# RC_Transmitter.net
KiCad netlist of a schematic drawn in EasyEDA Pro
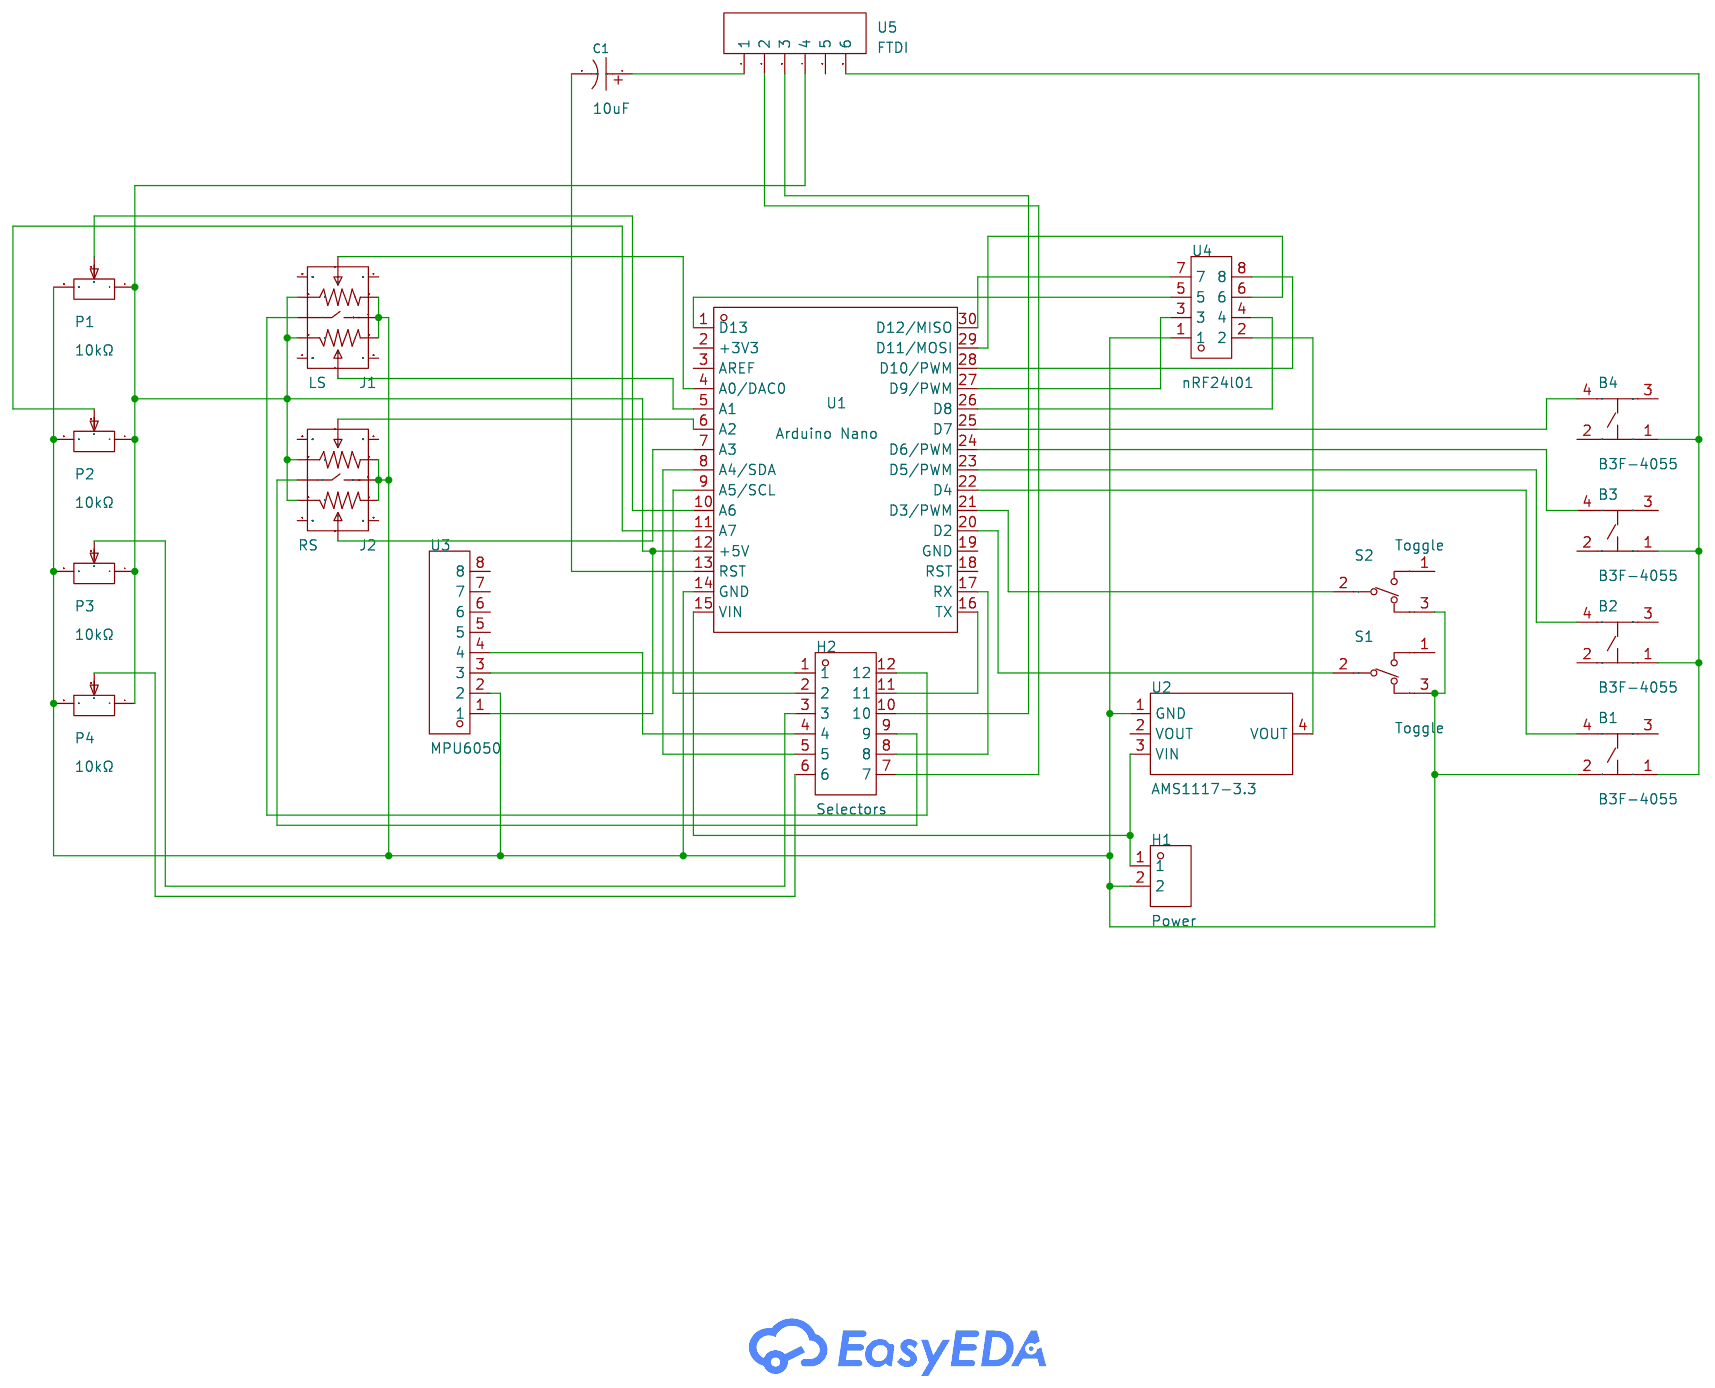
[diagram p0: schematic sheet]

(export (version "E")
  (design (tool "Eeschema 10.0.6"))
  (components
    (comp (ref "B1")
      (value "B3F-4055")
      (footprint "easyedapro:KEY-TH_4P-L12.0-W12.0-P5.00-LS13.4-EH")
      (fields (field (name "Manufacturer") "OMRON(欧姆龙)"))
      (libsource (lib "easyedapro") (part "B3F-4055"))
    )
    (comp (ref "B2")
      (value "B3F-4055")
      (footprint "easyedapro:KEY-TH_4P-L12.0-W12.0-P5.00-LS13.4-EH")
      (fields (field (name "Manufacturer") "OMRON(欧姆龙)"))
      (libsource (lib "easyedapro") (part "B3F-4055"))
    )
    (comp (ref "B3")
      (value "B3F-4055")
      (footprint "easyedapro:KEY-TH_4P-L12.0-W12.0-P5.00-LS13.4-EH")
      (fields (field (name "Manufacturer") "OMRON(欧姆龙)"))
      (libsource (lib "easyedapro") (part "B3F-4055"))
    )
    (comp (ref "B4")
      (value "B3F-4055")
      (footprint "easyedapro:KEY-TH_4P-L12.0-W12.0-P5.00-LS13.4-EH")
      (fields (field (name "Manufacturer") "OMRON(欧姆龙)"))
      (libsource (lib "easyedapro") (part "B3F-4055"))
    )
    (comp (ref "C1")
      (value "10uF")
      (footprint "easyedapro:CAP-TH_BD5.0-P2.00-D0.8-FD")
      (fields (field (name "Manufacturer Part") "RD1H106M05011PC") (field (name "Manufacturer") "SAMWHA(三和)"))
      (libsource (lib "easyedapro") (part "RD1H106M05011PC"))
    )
    (comp (ref "H1")
      (value "Power")
      (footprint "easyedapro:HDR-TH_2P-P2.54-V-M_5")
      (fields (field (name "Manufacturer") "HCTL(华灿天禄)"))
      (libsource (lib "easyedapro") (part "PZ254-1-02-Z-C"))
    )
    (comp (ref "H2")
      (value "Selectors")
      (footprint "easyedapro:HDR-TH_12P-P2.54-V-M-R3-C4-S2.54")
      (fields (field (name "Manufacturer") "hanxia(韩下)"))
      (libsource (lib "easyedapro") (part "HX PZ2.54-3X4P ZZ"))
    )
    (comp (ref "J1")
      (value "LS")
      (footprint "easyedapro:JOYTICK-TH_YF16S-FL7.2-B5KB-45-10-Y_1")
      (fields (field (name "Manufacturer") "YTL(亚特联)"))
      (libsource (lib "easyedapro") (part "YK16S-L7.2-B10KA(32-8)-G-A29"))
    )
    (comp (ref "J2")
      (value "RS")
      (footprint "easyedapro:JOYTICK-TH_YF16S-FL7.2-B5KB-45-10-Y_1")
      (fields (field (name "Manufacturer") "YTL(亚特联)"))
      (libsource (lib "easyedapro") (part "YK16S-L7.2-B10KA(32-8)-G-A29"))
    )
    (comp (ref "P1")
      (value "10kΩ")
      (footprint "easyedapro:RES-ADJ-TH_RK1631110U1Q")
      (description "Resistance: Tolerance:±20% Tolerance:±20% Rated Voltage:5V Power(Watts):100mW Turns:-")
      (fields
        (field (name "Manufacturer Part") "RK1631110U1Q")
        (field (name "Manufacturer") "ALPSALPINE(阿尔卑斯阿尔派)")
      )
      (libsource (lib "easyedapro") (part "RK1631110U1Q"))
    )
    (comp (ref "P2")
      (value "10kΩ")
      (footprint "easyedapro:RES-ADJ-TH_RK1631110U1Q")
      (description "Resistance: Tolerance:±20% Tolerance:±20% Rated Voltage:5V Power(Watts):100mW Turns:-")
      (fields
        (field (name "Manufacturer Part") "RK1631110U1Q")
        (field (name "Manufacturer") "ALPSALPINE(阿尔卑斯阿尔派)")
      )
      (libsource (lib "easyedapro") (part "RK1631110U1Q"))
    )
    (comp (ref "P3")
      (value "10kΩ")
      (footprint "easyedapro:RES-ADJ-TH_RK1631110U1Q")
      (description "Resistance: Tolerance:±20% Tolerance:±20% Rated Voltage:5V Power(Watts):100mW Turns:-")
      (fields
        (field (name "Manufacturer Part") "RK1631110U1Q")
        (field (name "Manufacturer") "ALPSALPINE(阿尔卑斯阿尔派)")
      )
      (libsource (lib "easyedapro") (part "RK1631110U1Q"))
    )
    (comp (ref "P4")
      (value "10kΩ")
      (footprint "easyedapro:RES-ADJ-TH_RK1631110U1Q")
      (description "Resistance: Tolerance:±20% Tolerance:±20% Rated Voltage:5V Power(Watts):100mW Turns:-")
      (fields
        (field (name "Manufacturer Part") "RK1631110U1Q")
        (field (name "Manufacturer") "ALPSALPINE(阿尔卑斯阿尔派)")
      )
      (libsource (lib "easyedapro") (part "RK1631110U1Q"))
    )
    (comp (ref "S1")
      (value "Toggle")
      (footprint "easyedapro:SW-TH_ST-0-103-A01")
      (fields (field (name "Manufacturer") "YUEN FUNG(源丰)"))
      (libsource (lib "easyedapro") (part "ST-0-103-A01-T000-RS"))
    )
    (comp (ref "S2")
      (value "Toggle")
      (footprint "easyedapro:SW-TH_ST-0-103-A01")
      (fields (field (name "Manufacturer") "YUEN FUNG(源丰)"))
      (libsource (lib "easyedapro") (part "ST-0-103-A01-T000-RS"))
    )
    (comp (ref "U1")
      (value "Arduino Nano")
      (footprint "easyedapro:MOD-TH_ABX00028")
      (fields (field (name "Manufacturer") "arduino"))
      (libsource (lib "easyedapro") (part "ABX00028"))
    )
    (comp (ref "U2")
      (value "AMS1117-3.3")
      (footprint "easyedapro:SOT-223-3_L6.5-W3.4-P2.30-LS7.0-BR")
      (fields (field (name "Manufacturer") "AMS"))
      (libsource (lib "easyedapro") (part "AMS1117-3.3"))
    )
    (comp (ref "U3")
      (value "MPU6050")
      (footprint "easyedapro:HDR-TH_8P-P2.54-V-F")
      (fields (field (name "Manufacturer") "kinghelm(金航标)"))
      (libsource (lib "easyedapro") (part "KH-2.54FH-1X8P-H8.5"))
    )
    (comp (ref "U4")
      (value "nRF24l01")
      (footprint "easyedapro:HDR-TH_8P-P2.54-V-F-R2-C4-S2.54")
      (fields (field (name "Manufacturer") "ZHOURI(洲日)"))
      (libsource (lib "easyedapro") (part "2.54-2*4"))
    )
    (comp (ref "U5")
      (value "FTDI")
      (footprint "easyedapro:HDR-TH_6P-P2.54-V-M-1")
      (fields (field (name "Manufacturer") "BOOMELE(博穆精密)"))
      (libsource (lib "easyedapro") (part "Header-Male-2.54_1x6"))
    )
  )
  (nets
    (net (code "1") (name "Net-(B1-Pad1)") (class "Default")
      (node (ref "B1") (pin "1") (pinfunction "1_1") (pintype "unspecified"))
      (node (ref "B2") (pin "1") (pinfunction "1_1") (pintype "unspecified"))
      (node (ref "B3") (pin "1") (pinfunction "1_1") (pintype "unspecified"))
      (node (ref "B4") (pin "1") (pinfunction "1_1") (pintype "unspecified"))
      (node (ref "U5") (pin "6") (pinfunction "6_6") (pintype "input"))
    )
    (net (code "2") (name "Net-(C1-Pad1)") (class "Default")
      (node (ref "C1") (pin "1") (pinfunction "1_1") (pintype "input"))
      (node (ref "U5") (pin "1") (pinfunction "1_1") (pintype "input"))
    )
    (net (code "3") (name "Net-(C1-Pad2)") (class "Default")
      (node (ref "C1") (pin "2") (pinfunction "2_2") (pintype "input"))
      (node (ref "U1") (pin "13") (pinfunction "RST_13") (pintype "unspecified"))
    )
    (net (code "4") (name "Net-(H2-Pad1)") (class "Default")
      (node (ref "H2") (pin "1") (pinfunction "1_1") (pintype "unspecified"))
      (node (ref "U3") (pin "3") (pinfunction "3_3") (pintype "unspecified"))
    )
    (net (code "5") (name "Net-(H2-Pad3)") (class "Default")
      (node (ref "H2") (pin "3") (pinfunction "3_3") (pintype "unspecified"))
      (node (ref "P3") (pin "2") (pinfunction "2_2") (pintype "input"))
    )
    (net (code "6") (name "Net-(H2-Pad4)") (class "Default")
      (node (ref "H2") (pin "4") (pinfunction "4_4") (pintype "unspecified"))
      (node (ref "U3") (pin "4") (pinfunction "4_4") (pintype "unspecified"))
    )
    (net (code "7") (name "Net-(H2-Pad6)") (class "Default")
      (node (ref "H2") (pin "6") (pinfunction "6_6") (pintype "unspecified"))
      (node (ref "P4") (pin "2") (pinfunction "2_2") (pintype "input"))
    )
    (net (code "8") (name "Net-(H2-Pad7)") (class "Default")
      (node (ref "H2") (pin "7") (pinfunction "7_7") (pintype "unspecified"))
      (node (ref "U5") (pin "2") (pinfunction "2_2") (pintype "input"))
    )
    (net (code "9") (name "Net-(H2-Pad9)") (class "Default")
      (node (ref "H2") (pin "9") (pinfunction "9_9") (pintype "unspecified"))
      (node (ref "J2") (pin "7") (pinfunction "7_7") (pintype "unspecified"))
    )
    (net (code "10") (name "Net-(H2-Pad10)") (class "Default")
      (node (ref "H2") (pin "10") (pinfunction "10_10") (pintype "unspecified"))
      (node (ref "U5") (pin "3") (pinfunction "3_3") (pintype "input"))
    )
    (net (code "11") (name "Net-(H2-Pad12)") (class "Default")
      (node (ref "H2") (pin "12") (pinfunction "12_12") (pintype "unspecified"))
      (node (ref "J1") (pin "7") (pinfunction "7_7") (pintype "unspecified"))
    )
    (net (code "12") (name "Net-(U1-+5V)") (class "Default")
      (node (ref "J1") (pin "3") (pinfunction "3_3") (pintype "unspecified"))
      (node (ref "J1") (pin "6") (pinfunction "6_6") (pintype "unspecified"))
      (node (ref "J2") (pin "3") (pinfunction "3_3") (pintype "unspecified"))
      (node (ref "J2") (pin "6") (pinfunction "6_6") (pintype "unspecified"))
      (node (ref "P1") (pin "1") (pinfunction "1_1") (pintype "input"))
      (node (ref "P2") (pin "1") (pinfunction "1_1") (pintype "input"))
      (node (ref "P3") (pin "1") (pinfunction "1_1") (pintype "input"))
      (node (ref "P4") (pin "1") (pinfunction "1_1") (pintype "input"))
      (node (ref "U1") (pin "12") (pinfunction "+5V_12") (pintype "unspecified"))
      (node (ref "U3") (pin "1") (pinfunction "1_1") (pintype "unspecified"))
      (node (ref "U5") (pin "4") (pinfunction "4_4") (pintype "input"))
    )
    (net (code "13") (name "Net-(U1-A0{slash}DAC0)") (class "Default")
      (node (ref "J1") (pin "2") (pinfunction "2_2") (pintype "unspecified"))
      (node (ref "U1") (pin "4") (pinfunction "A0/DAC0_4") (pintype "unspecified"))
    )
    (net (code "14") (name "Net-(U1-A1)") (class "Default")
      (node (ref "J1") (pin "5") (pinfunction "5_5") (pintype "unspecified"))
      (node (ref "U1") (pin "5") (pinfunction "A1_5") (pintype "unspecified"))
    )
    (net (code "15") (name "Net-(U1-A2)") (class "Default")
      (node (ref "J2") (pin "2") (pinfunction "2_2") (pintype "unspecified"))
      (node (ref "U1") (pin "6") (pinfunction "A2_6") (pintype "unspecified"))
    )
    (net (code "16") (name "Net-(U1-A3)") (class "Default")
      (node (ref "J2") (pin "5") (pinfunction "5_5") (pintype "unspecified"))
      (node (ref "U1") (pin "7") (pinfunction "A3_7") (pintype "unspecified"))
    )
    (net (code "17") (name "Net-(U1-A4{slash}SDA)") (class "Default")
      (node (ref "H2") (pin "5") (pinfunction "5_5") (pintype "unspecified"))
      (node (ref "U1") (pin "8") (pinfunction "A4/SDA_8") (pintype "unspecified"))
    )
    (net (code "18") (name "Net-(U1-A5{slash}SCL)") (class "Default")
      (node (ref "H2") (pin "2") (pinfunction "2_2") (pintype "unspecified"))
      (node (ref "U1") (pin "9") (pinfunction "A5/SCL_9") (pintype "unspecified"))
    )
    (net (code "19") (name "Net-(U1-A6)") (class "Default")
      (node (ref "P1") (pin "2") (pinfunction "2_2") (pintype "input"))
      (node (ref "U1") (pin "10") (pinfunction "A6_10") (pintype "unspecified"))
    )
    (net (code "20") (name "Net-(U1-A7)") (class "Default")
      (node (ref "P2") (pin "2") (pinfunction "2_2") (pintype "input"))
      (node (ref "U1") (pin "11") (pinfunction "A7_11") (pintype "unspecified"))
    )
    (net (code "21") (name "Net-(U1-D2)") (class "Default")
      (node (ref "S1") (pin "2") (pinfunction "2_2") (pintype "unspecified"))
      (node (ref "U1") (pin "20") (pinfunction "D2_20") (pintype "unspecified"))
    )
    (net (code "22") (name "Net-(U1-D3{slash}PWM)") (class "Default")
      (node (ref "S2") (pin "2") (pinfunction "2_2") (pintype "unspecified"))
      (node (ref "U1") (pin "21") (pinfunction "D3/PWM_21") (pintype "unspecified"))
    )
    (net (code "23") (name "Net-(U1-D4)") (class "Default")
      (node (ref "B1") (pin "4") (pinfunction "4_4") (pintype "unspecified"))
      (node (ref "U1") (pin "22") (pinfunction "D4_22") (pintype "unspecified"))
    )
    (net (code "24") (name "Net-(U1-D5{slash}PWM)") (class "Default")
      (node (ref "B2") (pin "4") (pinfunction "4_4") (pintype "unspecified"))
      (node (ref "U1") (pin "23") (pinfunction "D5/PWM_23") (pintype "unspecified"))
    )
    (net (code "25") (name "Net-(U1-D6{slash}PWM)") (class "Default")
      (node (ref "B3") (pin "4") (pinfunction "4_4") (pintype "unspecified"))
      (node (ref "U1") (pin "24") (pinfunction "D6/PWM_24") (pintype "unspecified"))
    )
    (net (code "26") (name "Net-(U1-D7)") (class "Default")
      (node (ref "B4") (pin "4") (pinfunction "4_4") (pintype "unspecified"))
      (node (ref "U1") (pin "25") (pinfunction "D7_25") (pintype "unspecified"))
    )
    (net (code "27") (name "Net-(U1-D8)") (class "Default")
      (node (ref "U1") (pin "26") (pinfunction "D8_26") (pintype "unspecified"))
      (node (ref "U4") (pin "4") (pinfunction "4_4") (pintype "unspecified"))
    )
    (net (code "28") (name "Net-(U1-D9{slash}PWM)") (class "Default")
      (node (ref "U1") (pin "27") (pinfunction "D9/PWM_27") (pintype "unspecified"))
      (node (ref "U4") (pin "3") (pinfunction "3_3") (pintype "unspecified"))
    )
    (net (code "29") (name "Net-(U1-D10{slash}PWM)") (class "Default")
      (node (ref "U1") (pin "28") (pinfunction "D10/PWM_28") (pintype "unspecified"))
      (node (ref "U4") (pin "8") (pinfunction "8_8") (pintype "unspecified"))
    )
    (net (code "30") (name "Net-(U1-D11{slash}MOSI)") (class "Default")
      (node (ref "U1") (pin "29") (pinfunction "D11/MOSI_29") (pintype "unspecified"))
      (node (ref "U4") (pin "6") (pinfunction "6_6") (pintype "unspecified"))
    )
    (net (code "31") (name "Net-(U1-D12{slash}MISO)") (class "Default")
      (node (ref "U1") (pin "30") (pinfunction "D12/MISO_30") (pintype "unspecified"))
      (node (ref "U4") (pin "7") (pinfunction "7_7") (pintype "unspecified"))
    )
    (net (code "32") (name "Net-(U1-D13)") (class "Default")
      (node (ref "U1") (pin "1") (pinfunction "D13_1") (pintype "unspecified"))
      (node (ref "U4") (pin "5") (pinfunction "5_5") (pintype "unspecified"))
    )
    (net (code "33") (name "Net-(U1-RX)") (class "Default")
      (node (ref "H2") (pin "8") (pinfunction "8_8") (pintype "unspecified"))
      (node (ref "U1") (pin "17") (pinfunction "RX_17") (pintype "unspecified"))
    )
    (net (code "34") (name "Net-(U1-TX)") (class "Default")
      (node (ref "H2") (pin "11") (pinfunction "11_11") (pintype "unspecified"))
      (node (ref "U1") (pin "16") (pinfunction "TX_16") (pintype "unspecified"))
    )
    (net (code "35") (name "Net-(U1-VIN)") (class "Default")
      (node (ref "H1") (pin "1") (pinfunction "1_1") (pintype "unspecified"))
      (node (ref "U1") (pin "15") (pinfunction "VIN_15") (pintype "unspecified"))
      (node (ref "U2") (pin "3") (pinfunction "VIN_3") (pintype "unspecified"))
    )
    (net (code "36") (name "Net-(U2-GND)") (class "Default")
      (node (ref "B1") (pin "2") (pinfunction "2_2") (pintype "unspecified"))
      (node (ref "H1") (pin "2") (pinfunction "2_2") (pintype "unspecified"))
      (node (ref "J1") (pin "1") (pinfunction "1_1") (pintype "unspecified"))
      (node (ref "J1") (pin "4") (pinfunction "4_4") (pintype "unspecified"))
      (node (ref "J1") (pin "8") (pinfunction "8_8") (pintype "unspecified"))
      (node (ref "J2") (pin "1") (pinfunction "1_1") (pintype "unspecified"))
      (node (ref "J2") (pin "4") (pinfunction "4_4") (pintype "unspecified"))
      (node (ref "J2") (pin "8") (pinfunction "8_8") (pintype "unspecified"))
      (node (ref "P1") (pin "3") (pinfunction "3_3") (pintype "input"))
      (node (ref "P2") (pin "3") (pinfunction "3_3") (pintype "input"))
      (node (ref "P3") (pin "3") (pinfunction "3_3") (pintype "input"))
      (node (ref "P4") (pin "3") (pinfunction "3_3") (pintype "input"))
      (node (ref "S1") (pin "3") (pinfunction "3_3") (pintype "unspecified"))
      (node (ref "S2") (pin "3") (pinfunction "3_3") (pintype "unspecified"))
      (node (ref "U1") (pin "14") (pinfunction "GND_14") (pintype "unspecified"))
      (node (ref "U2") (pin "1") (pinfunction "GND_1") (pintype "unspecified"))
      (node (ref "U3") (pin "2") (pinfunction "2_2") (pintype "unspecified"))
      (node (ref "U4") (pin "1") (pinfunction "1_1") (pintype "unspecified"))
    )
    (net (code "37") (name "Net-(U2-VOUT-Pad4)") (class "Default")
      (node (ref "U2") (pin "4") (pinfunction "VOUT_4") (pintype "unspecified"))
      (node (ref "U4") (pin "2") (pinfunction "2_2") (pintype "unspecified"))
    )
    (net (code "38") (name "unconnected-(B1-Pad3)") (class "Default")
      (node (ref "B1") (pin "3") (pinfunction "3_3") (pintype "unspecified"))
    )
    (net (code "39") (name "unconnected-(B2-Pad2)") (class "Default")
      (node (ref "B2") (pin "2") (pinfunction "2_2") (pintype "unspecified"))
    )
    (net (code "40") (name "unconnected-(B2-Pad3)") (class "Default")
      (node (ref "B2") (pin "3") (pinfunction "3_3") (pintype "unspecified"))
    )
    (net (code "41") (name "unconnected-(B3-Pad2)") (class "Default")
      (node (ref "B3") (pin "2") (pinfunction "2_2") (pintype "unspecified"))
    )
    (net (code "42") (name "unconnected-(B3-Pad3)") (class "Default")
      (node (ref "B3") (pin "3") (pinfunction "3_3") (pintype "unspecified"))
    )
    (net (code "43") (name "unconnected-(B4-Pad2)") (class "Default")
      (node (ref "B4") (pin "2") (pinfunction "2_2") (pintype "unspecified"))
    )
    (net (code "44") (name "unconnected-(B4-Pad3)") (class "Default")
      (node (ref "B4") (pin "3") (pinfunction "3_3") (pintype "unspecified"))
    )
    (net (code "45") (name "unconnected-(J1-shell-Pad9)") (class "Default")
      (node (ref "J1") (pin "9") (pinfunction "shell_9") (pintype "unspecified"))
    )
    (net (code "46") (name "unconnected-(J1-shell-Pad10)") (class "Default")
      (node (ref "J1") (pin "10") (pinfunction "shell_10") (pintype "unspecified"))
    )
    (net (code "47") (name "unconnected-(J1-shell-Pad11)") (class "Default")
      (node (ref "J1") (pin "11") (pinfunction "shell_11") (pintype "unspecified"))
    )
    (net (code "48") (name "unconnected-(J1-shell-Pad12)") (class "Default")
      (node (ref "J1") (pin "12") (pinfunction "shell_12") (pintype "unspecified"))
    )
    (net (code "49") (name "unconnected-(J2-shell-Pad9)") (class "Default")
      (node (ref "J2") (pin "9") (pinfunction "shell_9") (pintype "unspecified"))
    )
    (net (code "50") (name "unconnected-(J2-shell-Pad10)") (class "Default")
      (node (ref "J2") (pin "10") (pinfunction "shell_10") (pintype "unspecified"))
    )
    (net (code "51") (name "unconnected-(J2-shell-Pad11)") (class "Default")
      (node (ref "J2") (pin "11") (pinfunction "shell_11") (pintype "unspecified"))
    )
    (net (code "52") (name "unconnected-(J2-shell-Pad12)") (class "Default")
      (node (ref "J2") (pin "12") (pinfunction "shell_12") (pintype "unspecified"))
    )
    (net (code "53") (name "unconnected-(S1-Pad1)") (class "Default")
      (node (ref "S1") (pin "1") (pinfunction "1_1") (pintype "unspecified"))
    )
    (net (code "54") (name "unconnected-(S2-Pad1)") (class "Default")
      (node (ref "S2") (pin "1") (pinfunction "1_1") (pintype "unspecified"))
    )
    (net (code "55") (name "unconnected-(U1-+3V3-Pad2)") (class "Default")
      (node (ref "U1") (pin "2") (pinfunction "+3V3_2") (pintype "unspecified"))
    )
    (net (code "56") (name "unconnected-(U1-AREF-Pad3)") (class "Default")
      (node (ref "U1") (pin "3") (pinfunction "AREF_3") (pintype "unspecified"))
    )
    (net (code "57") (name "unconnected-(U1-GND-Pad19)") (class "Default")
      (node (ref "U1") (pin "19") (pinfunction "GND_19") (pintype "unspecified"))
    )
    (net (code "58") (name "unconnected-(U1-RST-Pad18)") (class "Default")
      (node (ref "U1") (pin "18") (pinfunction "RST_18") (pintype "unspecified"))
    )
    (net (code "59") (name "unconnected-(U2-VOUT-Pad2)") (class "Default")
      (node (ref "U2") (pin "2") (pinfunction "VOUT_2") (pintype "unspecified"))
    )
    (net (code "60") (name "unconnected-(U3-Pad5)") (class "Default")
      (node (ref "U3") (pin "5") (pinfunction "5_5") (pintype "unspecified"))
    )
    (net (code "61") (name "unconnected-(U3-Pad6)") (class "Default")
      (node (ref "U3") (pin "6") (pinfunction "6_6") (pintype "unspecified"))
    )
    (net (code "62") (name "unconnected-(U3-Pad7)") (class "Default")
      (node (ref "U3") (pin "7") (pinfunction "7_7") (pintype "unspecified"))
    )
    (net (code "63") (name "unconnected-(U3-Pad8)") (class "Default")
      (node (ref "U3") (pin "8") (pinfunction "8_8") (pintype "unspecified"))
    )
    (net (code "64") (name "unconnected-(U5-Pad5)") (class "Default")
      (node (ref "U5") (pin "5") (pinfunction "5_5") (pintype "input"))
    )
  )
)
